# SCH_stm32_v6_2024-12-07.net
KiCad netlist of a schematic drawn in EasyEDA
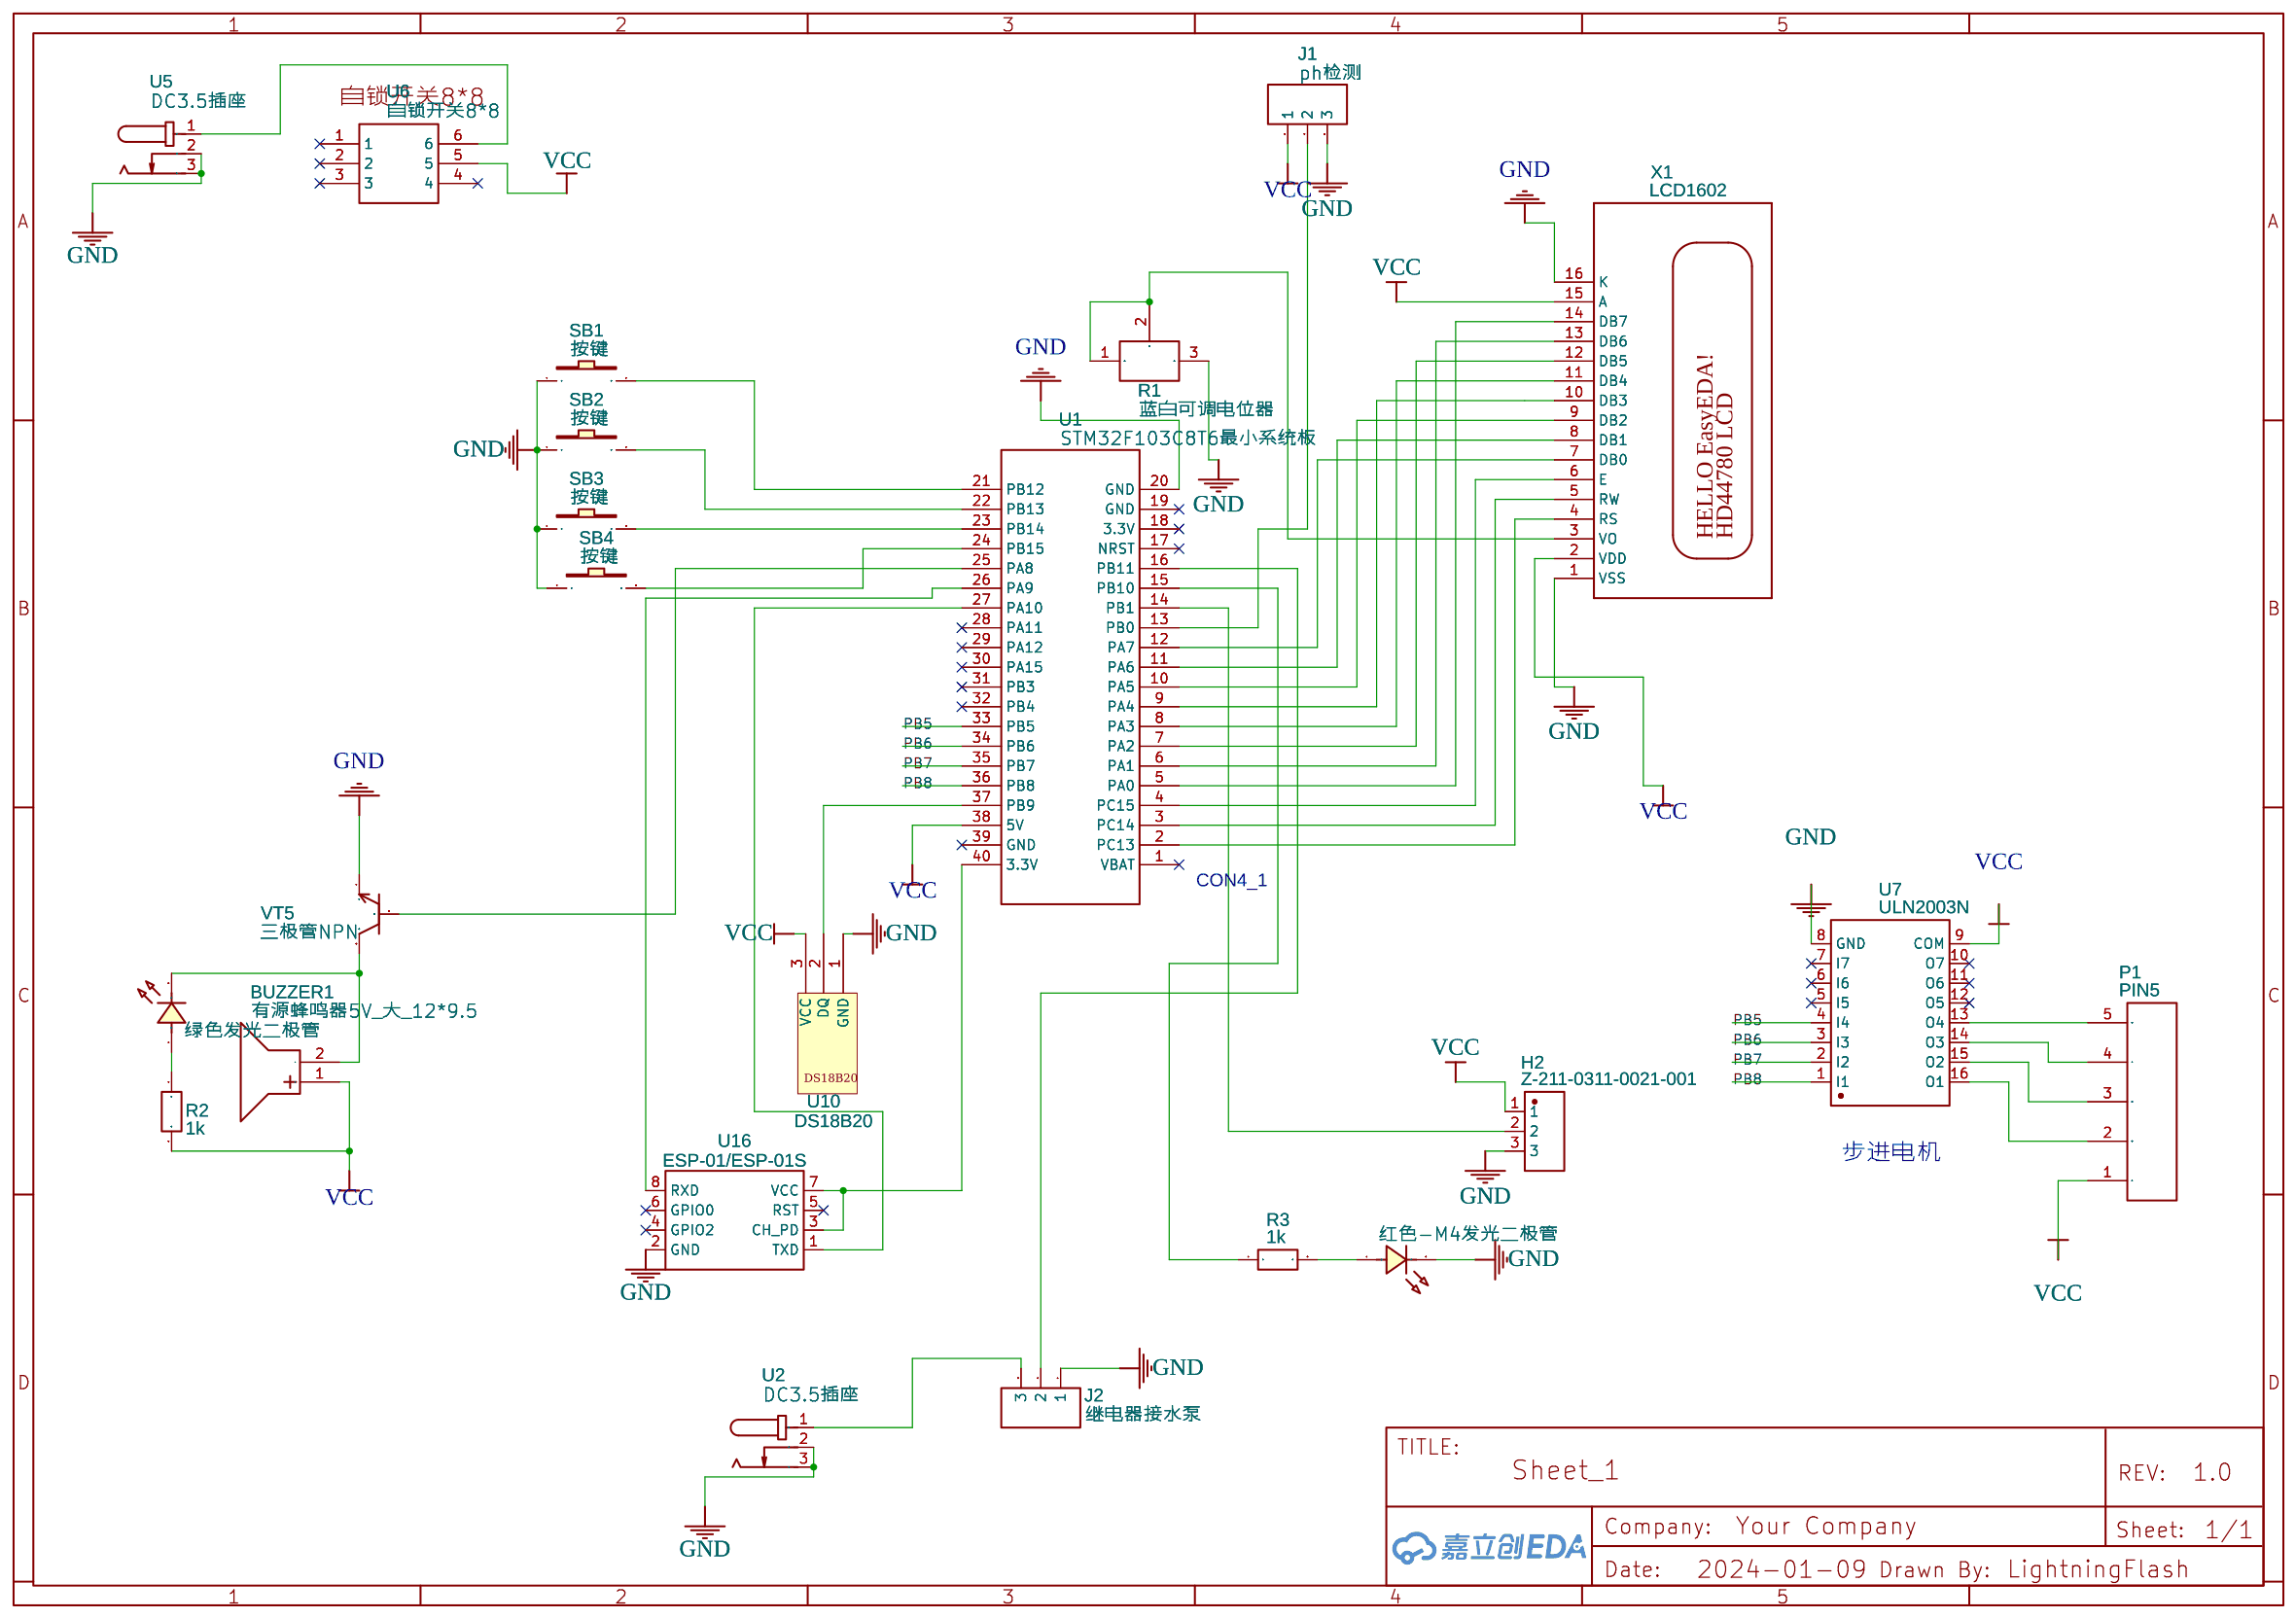
[diagram p0: schematic sheet]

(export (version "E")
  (design (tool "Eeschema 10.0.6"))
  (components
    (comp (ref "BUZZER1")
      (value "有源蜂鸣器5V_大_12*9.5")
      (fields (field (name "Manufacturer Part") "ZL-DCY12095-2305P-7.6") (field (name "Manufacturer") "ZLFY"))
      (libsource (lib "") (part "有源蜂鸣器5V_大_12*9.5"))
    )
    (comp (ref "H2")
      (value "Z-211-0311-0021-001")
      (fields (field (name "Manufacturer") "ZHENGLING"))
      (libsource (lib "") (part "Z-211-0311-0021-001"))
    )
    (comp (ref "J1") (value "ph检测") (libsource (lib "") (part "HDR-M-2.54_1x3")))
    (comp (ref "J2") (value "继电器接水泵") (libsource (lib "") (part "HDR-M-2.54_1x3_1")))
    (comp (ref "NO2")
      (value "绿色发光二极管")
      (fields (field (name "Manufacturer Part") "红色-M4发光二极管"))
      (libsource (lib "") (part "红色-M4发光二极管"))
    )
    (comp (ref "NO3") (value "红色-M4发光二极管") (libsource (lib "") (part "红色-M4发光二极管_1")))
    (comp (ref "P1") (value "PIN5") (libsource (lib "") (part "PIN5")))
    (comp (ref "R1") (value "蓝白可调电位器") (libsource (lib "") (part "蓝白可调电位器")))
    (comp (ref "R2") (value "1k") (libsource (lib "") (part "R_0603_EU_1")))
    (comp (ref "R3") (value "1k") (libsource (lib "") (part "R_0603_EU")))
    (comp (ref "SB1") (value "按键") (libsource (lib "") (part "按键")))
    (comp (ref "SB2") (value "按键") (libsource (lib "") (part "按键")))
    (comp (ref "SB3") (value "按键") (libsource (lib "") (part "按键")))
    (comp (ref "SB4") (value "按键") (libsource (lib "") (part "按键")))
    (comp (ref "U1") (value "STM32F103C8T6最小系统板") (libsource (lib "") (part "STM32F103C8T6最小系统板")))
    (comp (ref "U2") (value "DC3.5插座") (libsource (lib "") (part "DC3.5插座")))
    (comp (ref "U5") (value "DC3.5插座") (libsource (lib "") (part "DC3.5插座")))
    (comp (ref "U6") (value "自锁开关8*8") (libsource (lib "") (part "自锁开关8*8")))
    (comp (ref "U7")
      (value "ULN2003N")
      (fields (field (name "Manufacturer") "HGSEMI"))
      (libsource (lib "") (part "ULN2003N"))
    )
    (comp (ref "U10") (value "DS18B20") (libsource (lib "") (part "DS18B20")))
    (comp (ref "U16") (value "ESP-01/ESP-01S") (libsource (lib "") (part "ESP-01/ESP-01S")))
    (comp (ref "VT5") (value "三极管NPN") (libsource (lib "") (part "三极管NPN")))
    (comp (ref "X1") (value "LCD1602") (libsource (lib "") (part "LCD1602")))
  )
  (nets
    (net (code "1") (name "/PB5") (class "Default")
      (node (ref "U1") (pin "33") (pinfunction "PB5_33") (pintype "unspecified"))
      (node (ref "U7") (pin "4") (pinfunction "I4_4") (pintype "unspecified"))
    )
    (net (code "2") (name "/PB6") (class "Default")
      (node (ref "U1") (pin "34") (pinfunction "PB6_34") (pintype "unspecified"))
      (node (ref "U7") (pin "3") (pinfunction "I3_3") (pintype "unspecified"))
    )
    (net (code "3") (name "/PB7") (class "Default")
      (node (ref "U1") (pin "35") (pinfunction "PB7_35") (pintype "unspecified"))
      (node (ref "U7") (pin "2") (pinfunction "I2_2") (pintype "unspecified"))
    )
    (net (code "4") (name "/PB8") (class "Default")
      (node (ref "U1") (pin "36") (pinfunction "PB8_36") (pintype "unspecified"))
      (node (ref "U7") (pin "1") (pinfunction "I1_1") (pintype "unspecified"))
    )
    (net (code "5") (name "GND") (class "Default")
      (node (ref "H2") (pin "3") (pinfunction "3_3") (pintype "unspecified"))
      (node (ref "J1") (pin "3") (pinfunction "3_3") (pintype "input"))
      (node (ref "J2") (pin "1") (pinfunction "1_1") (pintype "input"))
      (node (ref "NO3") (pin "2") (pinfunction "K_2") (pintype "unspecified"))
      (node (ref "R1") (pin "3") (pinfunction "3_3") (pintype "unspecified"))
      (node (ref "SB1") (pin "1") (pinfunction "1_1") (pintype "unspecified"))
      (node (ref "SB2") (pin "1") (pinfunction "1_1") (pintype "unspecified"))
      (node (ref "SB3") (pin "1") (pinfunction "1_1") (pintype "unspecified"))
      (node (ref "SB4") (pin "1") (pinfunction "1_1") (pintype "unspecified"))
      (node (ref "U1") (pin "20") (pinfunction "GND_20") (pintype "unspecified"))
      (node (ref "U10") (pin "1") (pinfunction "GND_1") (pintype "unspecified"))
      (node (ref "U16") (pin "2") (pinfunction "GND_2") (pintype "unspecified"))
      (node (ref "U2") (pin "2") (pinfunction "2_2") (pintype "unspecified"))
      (node (ref "U2") (pin "3") (pinfunction "3_3") (pintype "unspecified"))
      (node (ref "U5") (pin "2") (pinfunction "2_2") (pintype "unspecified"))
      (node (ref "U5") (pin "3") (pinfunction "3_3") (pintype "unspecified"))
      (node (ref "U7") (pin "8") (pinfunction "GND_8") (pintype "unspecified"))
      (node (ref "VT5") (pin "1") (pinfunction "1_1") (pintype "unspecified"))
      (node (ref "X1") (pin "1") (pinfunction "VSS_1") (pintype "unspecified"))
      (node (ref "X1") (pin "16") (pinfunction "K_16") (pintype "input"))
    )
    (net (code "6") (name "Net-(BUZZER1--)") (class "Default")
      (node (ref "BUZZER1") (pin "2") (pinfunction "-_2") (pintype "unspecified"))
      (node (ref "NO2") (pin "2") (pinfunction "K_2") (pintype "unspecified"))
      (node (ref "VT5") (pin "3") (pinfunction "3_3") (pintype "unspecified"))
    )
    (net (code "7") (name "Net-(J2-Pad3)") (class "Default")
      (node (ref "J2") (pin "3") (pinfunction "3_3") (pintype "input"))
      (node (ref "U2") (pin "1") (pinfunction "1_1") (pintype "unspecified"))
    )
    (net (code "8") (name "Net-(NO2-A)") (class "Default")
      (node (ref "NO2") (pin "1") (pinfunction "A_1") (pintype "unspecified"))
      (node (ref "R2") (pin "1") (pinfunction "1_1") (pintype "unspecified"))
    )
    (net (code "9") (name "Net-(NO3-A)") (class "Default")
      (node (ref "NO3") (pin "1") (pinfunction "A_1") (pintype "unspecified"))
      (node (ref "R3") (pin "2") (pinfunction "2_2") (pintype "unspecified"))
    )
    (net (code "10") (name "Net-(R1-1)") (class "Default")
      (node (ref "R1") (pin "1") (pinfunction "2_1") (pintype "unspecified"))
      (node (ref "R1") (pin "2") (pinfunction "1_2") (pintype "unspecified"))
      (node (ref "X1") (pin "3") (pinfunction "VO_3") (pintype "input"))
    )
    (net (code "11") (name "Net-(U1-PA0)") (class "Default")
      (node (ref "U1") (pin "5") (pinfunction "PA0_5") (pintype "unspecified"))
      (node (ref "X1") (pin "14") (pinfunction "DB7_14") (pintype "unspecified"))
    )
    (net (code "12") (name "Net-(U1-PA1)") (class "Default")
      (node (ref "U1") (pin "6") (pinfunction "PA1_6") (pintype "unspecified"))
      (node (ref "X1") (pin "13") (pinfunction "DB6_13") (pintype "unspecified"))
    )
    (net (code "13") (name "Net-(U1-PA2)") (class "Default")
      (node (ref "U1") (pin "7") (pinfunction "PA2_7") (pintype "unspecified"))
      (node (ref "X1") (pin "12") (pinfunction "DB5_12") (pintype "unspecified"))
    )
    (net (code "14") (name "Net-(U1-PA3)") (class "Default")
      (node (ref "U1") (pin "8") (pinfunction "PA3_8") (pintype "unspecified"))
      (node (ref "X1") (pin "11") (pinfunction "DB4_11") (pintype "unspecified"))
    )
    (net (code "15") (name "Net-(U1-PA4)") (class "Default")
      (node (ref "U1") (pin "9") (pinfunction "PA4_9") (pintype "unspecified"))
      (node (ref "X1") (pin "10") (pinfunction "DB3_10") (pintype "unspecified"))
    )
    (net (code "16") (name "Net-(U1-PA5)") (class "Default")
      (node (ref "U1") (pin "10") (pinfunction "PA5_10") (pintype "unspecified"))
      (node (ref "X1") (pin "9") (pinfunction "DB2_9") (pintype "unspecified"))
    )
    (net (code "17") (name "Net-(U1-PA6)") (class "Default")
      (node (ref "U1") (pin "11") (pinfunction "PA6_11") (pintype "unspecified"))
      (node (ref "X1") (pin "8") (pinfunction "DB1_8") (pintype "unspecified"))
    )
    (net (code "18") (name "Net-(U1-PA7)") (class "Default")
      (node (ref "U1") (pin "12") (pinfunction "PA7_12") (pintype "unspecified"))
      (node (ref "X1") (pin "7") (pinfunction "DB0_7") (pintype "unspecified"))
    )
    (net (code "19") (name "Net-(U1-PA8)") (class "Default")
      (node (ref "U1") (pin "25") (pinfunction "PA8_25") (pintype "unspecified"))
      (node (ref "VT5") (pin "2") (pinfunction "2_2") (pintype "unspecified"))
    )
    (net (code "20") (name "Net-(U1-PA9)") (class "Default")
      (node (ref "U1") (pin "26") (pinfunction "PA9_26") (pintype "unspecified"))
      (node (ref "U16") (pin "8") (pinfunction "RXD_8") (pintype "unspecified"))
    )
    (net (code "21") (name "Net-(U1-PA10)") (class "Default")
      (node (ref "U1") (pin "27") (pinfunction "PA10_27") (pintype "unspecified"))
      (node (ref "U16") (pin "1") (pinfunction "TXD_1") (pintype "unspecified"))
    )
    (net (code "22") (name "Net-(U1-PB0)") (class "Default")
      (node (ref "J1") (pin "2") (pinfunction "2_2") (pintype "input"))
      (node (ref "U1") (pin "13") (pinfunction "PB0_13") (pintype "unspecified"))
    )
    (net (code "23") (name "Net-(U1-PB1)") (class "Default")
      (node (ref "H2") (pin "2") (pinfunction "2_2") (pintype "unspecified"))
      (node (ref "U1") (pin "14") (pinfunction "PB1_14") (pintype "unspecified"))
    )
    (net (code "24") (name "Net-(U1-PB9)") (class "Default")
      (node (ref "U1") (pin "37") (pinfunction "PB9_37") (pintype "unspecified"))
      (node (ref "U10") (pin "2") (pinfunction "DQ_2") (pintype "unspecified"))
    )
    (net (code "25") (name "Net-(U1-PB10)") (class "Default")
      (node (ref "R3") (pin "1") (pinfunction "1_1") (pintype "unspecified"))
      (node (ref "U1") (pin "15") (pinfunction "PB10_15") (pintype "unspecified"))
    )
    (net (code "26") (name "Net-(U1-PB11)") (class "Default")
      (node (ref "J2") (pin "2") (pinfunction "2_2") (pintype "input"))
      (node (ref "U1") (pin "16") (pinfunction "PB11_16") (pintype "unspecified"))
    )
    (net (code "27") (name "Net-(U1-PB12)") (class "Default")
      (node (ref "SB1") (pin "2") (pinfunction "2_2") (pintype "unspecified"))
      (node (ref "U1") (pin "21") (pinfunction "PB12_21") (pintype "unspecified"))
    )
    (net (code "28") (name "Net-(U1-PB13)") (class "Default")
      (node (ref "SB2") (pin "2") (pinfunction "2_2") (pintype "unspecified"))
      (node (ref "U1") (pin "22") (pinfunction "PB13_22") (pintype "unspecified"))
    )
    (net (code "29") (name "Net-(U1-PB14)") (class "Default")
      (node (ref "SB3") (pin "2") (pinfunction "2_2") (pintype "unspecified"))
      (node (ref "U1") (pin "23") (pinfunction "PB14_23") (pintype "unspecified"))
    )
    (net (code "30") (name "Net-(U1-PB15)") (class "Default")
      (node (ref "SB4") (pin "2") (pinfunction "2_2") (pintype "unspecified"))
      (node (ref "U1") (pin "24") (pinfunction "PB15_24") (pintype "unspecified"))
    )
    (net (code "31") (name "Net-(U1-PC13)") (class "Default")
      (node (ref "U1") (pin "2") (pinfunction "PC13_2") (pintype "unspecified"))
      (node (ref "X1") (pin "4") (pinfunction "RS_4") (pintype "input"))
    )
    (net (code "32") (name "Net-(U1-PC14)") (class "Default")
      (node (ref "U1") (pin "3") (pinfunction "PC14_3") (pintype "unspecified"))
      (node (ref "X1") (pin "5") (pinfunction "RW_5") (pintype "input"))
    )
    (net (code "33") (name "Net-(U1-PC15)") (class "Default")
      (node (ref "U1") (pin "4") (pinfunction "PC15_4") (pintype "unspecified"))
      (node (ref "X1") (pin "6") (pinfunction "E_6") (pintype "input"))
    )
    (net (code "34") (name "Net-(U5-Pad1)") (class "Default")
      (node (ref "U5") (pin "1") (pinfunction "1_1") (pintype "unspecified"))
      (node (ref "U6") (pin "6") (pinfunction "6_6") (pintype "unspecified"))
    )
    (net (code "35") (name "Net-(U7-O1)") (class "Default")
      (node (ref "P1") (pin "2") (pinfunction "2_2") (pintype "unspecified"))
      (node (ref "U7") (pin "16") (pinfunction "O1_16") (pintype "unspecified"))
    )
    (net (code "36") (name "Net-(U7-O2)") (class "Default")
      (node (ref "P1") (pin "3") (pinfunction "3_3") (pintype "unspecified"))
      (node (ref "U7") (pin "15") (pinfunction "O2_15") (pintype "unspecified"))
    )
    (net (code "37") (name "Net-(U7-O3)") (class "Default")
      (node (ref "P1") (pin "4") (pinfunction "4_4") (pintype "unspecified"))
      (node (ref "U7") (pin "14") (pinfunction "O3_14") (pintype "unspecified"))
    )
    (net (code "38") (name "Net-(U7-O4)") (class "Default")
      (node (ref "P1") (pin "5") (pinfunction "5_5") (pintype "unspecified"))
      (node (ref "U7") (pin "13") (pinfunction "O4_13") (pintype "unspecified"))
    )
    (net (code "39") (name "Net-(U16-CH_PD)") (class "Default")
      (node (ref "U1") (pin "40") (pinfunction "3.3V_40") (pintype "unspecified"))
      (node (ref "U16") (pin "3") (pinfunction "CH_PD_3") (pintype "unspecified"))
      (node (ref "U16") (pin "7") (pinfunction "VCC_7") (pintype "unspecified"))
    )
    (net (code "40") (name "VCC") (class "Default")
      (node (ref "BUZZER1") (pin "1") (pinfunction "+_1") (pintype "unspecified"))
      (node (ref "H2") (pin "1") (pinfunction "1_1") (pintype "unspecified"))
      (node (ref "J1") (pin "1") (pinfunction "1_1") (pintype "input"))
      (node (ref "P1") (pin "1") (pinfunction "1_1") (pintype "unspecified"))
      (node (ref "R2") (pin "2") (pinfunction "2_2") (pintype "unspecified"))
      (node (ref "U1") (pin "38") (pinfunction "5V_38") (pintype "unspecified"))
      (node (ref "U10") (pin "3") (pinfunction "VCC_3") (pintype "unspecified"))
      (node (ref "U6") (pin "5") (pinfunction "5_5") (pintype "unspecified"))
      (node (ref "U7") (pin "9") (pinfunction "COM_9") (pintype "unspecified"))
      (node (ref "X1") (pin "15") (pinfunction "A_15") (pintype "input"))
      (node (ref "X1") (pin "2") (pinfunction "VDD_2") (pintype "unspecified"))
    )
    (net (code "41") (name "unconnected-(U1-3.3V-Pad18)") (class "Default")
      (node (ref "U1") (pin "18") (pinfunction "3.3V_18") (pintype "unspecified+no_connect"))
    )
    (net (code "42") (name "unconnected-(U1-GND-Pad19)") (class "Default")
      (node (ref "U1") (pin "19") (pinfunction "GND_19") (pintype "unspecified+no_connect"))
    )
    (net (code "43") (name "unconnected-(U1-GND-Pad39)") (class "Default")
      (node (ref "U1") (pin "39") (pinfunction "GND_39") (pintype "unspecified+no_connect"))
    )
    (net (code "44") (name "unconnected-(U1-NRST-Pad17)") (class "Default")
      (node (ref "U1") (pin "17") (pinfunction "NRST_17") (pintype "unspecified+no_connect"))
    )
    (net (code "45") (name "unconnected-(U1-PA11-Pad28)") (class "Default")
      (node (ref "U1") (pin "28") (pinfunction "PA11_28") (pintype "unspecified+no_connect"))
    )
    (net (code "46") (name "unconnected-(U1-PA12-Pad29)") (class "Default")
      (node (ref "U1") (pin "29") (pinfunction "PA12_29") (pintype "unspecified+no_connect"))
    )
    (net (code "47") (name "unconnected-(U1-PA15-Pad30)") (class "Default")
      (node (ref "U1") (pin "30") (pinfunction "PA15_30") (pintype "unspecified+no_connect"))
    )
    (net (code "48") (name "unconnected-(U1-PB3-Pad31)") (class "Default")
      (node (ref "U1") (pin "31") (pinfunction "PB3_31") (pintype "unspecified+no_connect"))
    )
    (net (code "49") (name "unconnected-(U1-PB4-Pad32)") (class "Default")
      (node (ref "U1") (pin "32") (pinfunction "PB4_32") (pintype "unspecified+no_connect"))
    )
    (net (code "50") (name "unconnected-(U1-VBAT-Pad1)") (class "Default")
      (node (ref "U1") (pin "1") (pinfunction "VBAT_1") (pintype "unspecified+no_connect"))
    )
    (net (code "51") (name "unconnected-(U6-Pad1)") (class "Default")
      (node (ref "U6") (pin "1") (pinfunction "1_1") (pintype "unspecified+no_connect"))
    )
    (net (code "52") (name "unconnected-(U6-Pad2)") (class "Default")
      (node (ref "U6") (pin "2") (pinfunction "2_2") (pintype "unspecified+no_connect"))
    )
    (net (code "53") (name "unconnected-(U6-Pad3)") (class "Default")
      (node (ref "U6") (pin "3") (pinfunction "3_3") (pintype "unspecified+no_connect"))
    )
    (net (code "54") (name "unconnected-(U6-Pad4)") (class "Default")
      (node (ref "U6") (pin "4") (pinfunction "4_4") (pintype "unspecified+no_connect"))
    )
    (net (code "55") (name "unconnected-(U7-I5-Pad5)") (class "Default")
      (node (ref "U7") (pin "5") (pinfunction "I5_5") (pintype "unspecified+no_connect"))
    )
    (net (code "56") (name "unconnected-(U7-I6-Pad6)") (class "Default")
      (node (ref "U7") (pin "6") (pinfunction "I6_6") (pintype "unspecified+no_connect"))
    )
    (net (code "57") (name "unconnected-(U7-I7-Pad7)") (class "Default")
      (node (ref "U7") (pin "7") (pinfunction "I7_7") (pintype "unspecified+no_connect"))
    )
    (net (code "58") (name "unconnected-(U7-O5-Pad12)") (class "Default")
      (node (ref "U7") (pin "12") (pinfunction "O5_12") (pintype "unspecified+no_connect"))
    )
    (net (code "59") (name "unconnected-(U7-O6-Pad11)") (class "Default")
      (node (ref "U7") (pin "11") (pinfunction "O6_11") (pintype "unspecified+no_connect"))
    )
    (net (code "60") (name "unconnected-(U7-O7-Pad10)") (class "Default")
      (node (ref "U7") (pin "10") (pinfunction "O7_10") (pintype "unspecified+no_connect"))
    )
    (net (code "61") (name "unconnected-(U16-GPIO0-Pad6)") (class "Default")
      (node (ref "U16") (pin "6") (pinfunction "GPIO0_6") (pintype "unspecified+no_connect"))
    )
    (net (code "62") (name "unconnected-(U16-GPIO2-Pad4)") (class "Default")
      (node (ref "U16") (pin "4") (pinfunction "GPIO2_4") (pintype "unspecified+no_connect"))
    )
    (net (code "63") (name "unconnected-(U16-RST-Pad5)") (class "Default")
      (node (ref "U16") (pin "5") (pinfunction "RST_5") (pintype "unspecified+no_connect"))
    )
  )
)
